# Camera-Board.net
KiCad netlist of a schematic drawn in EAGLE
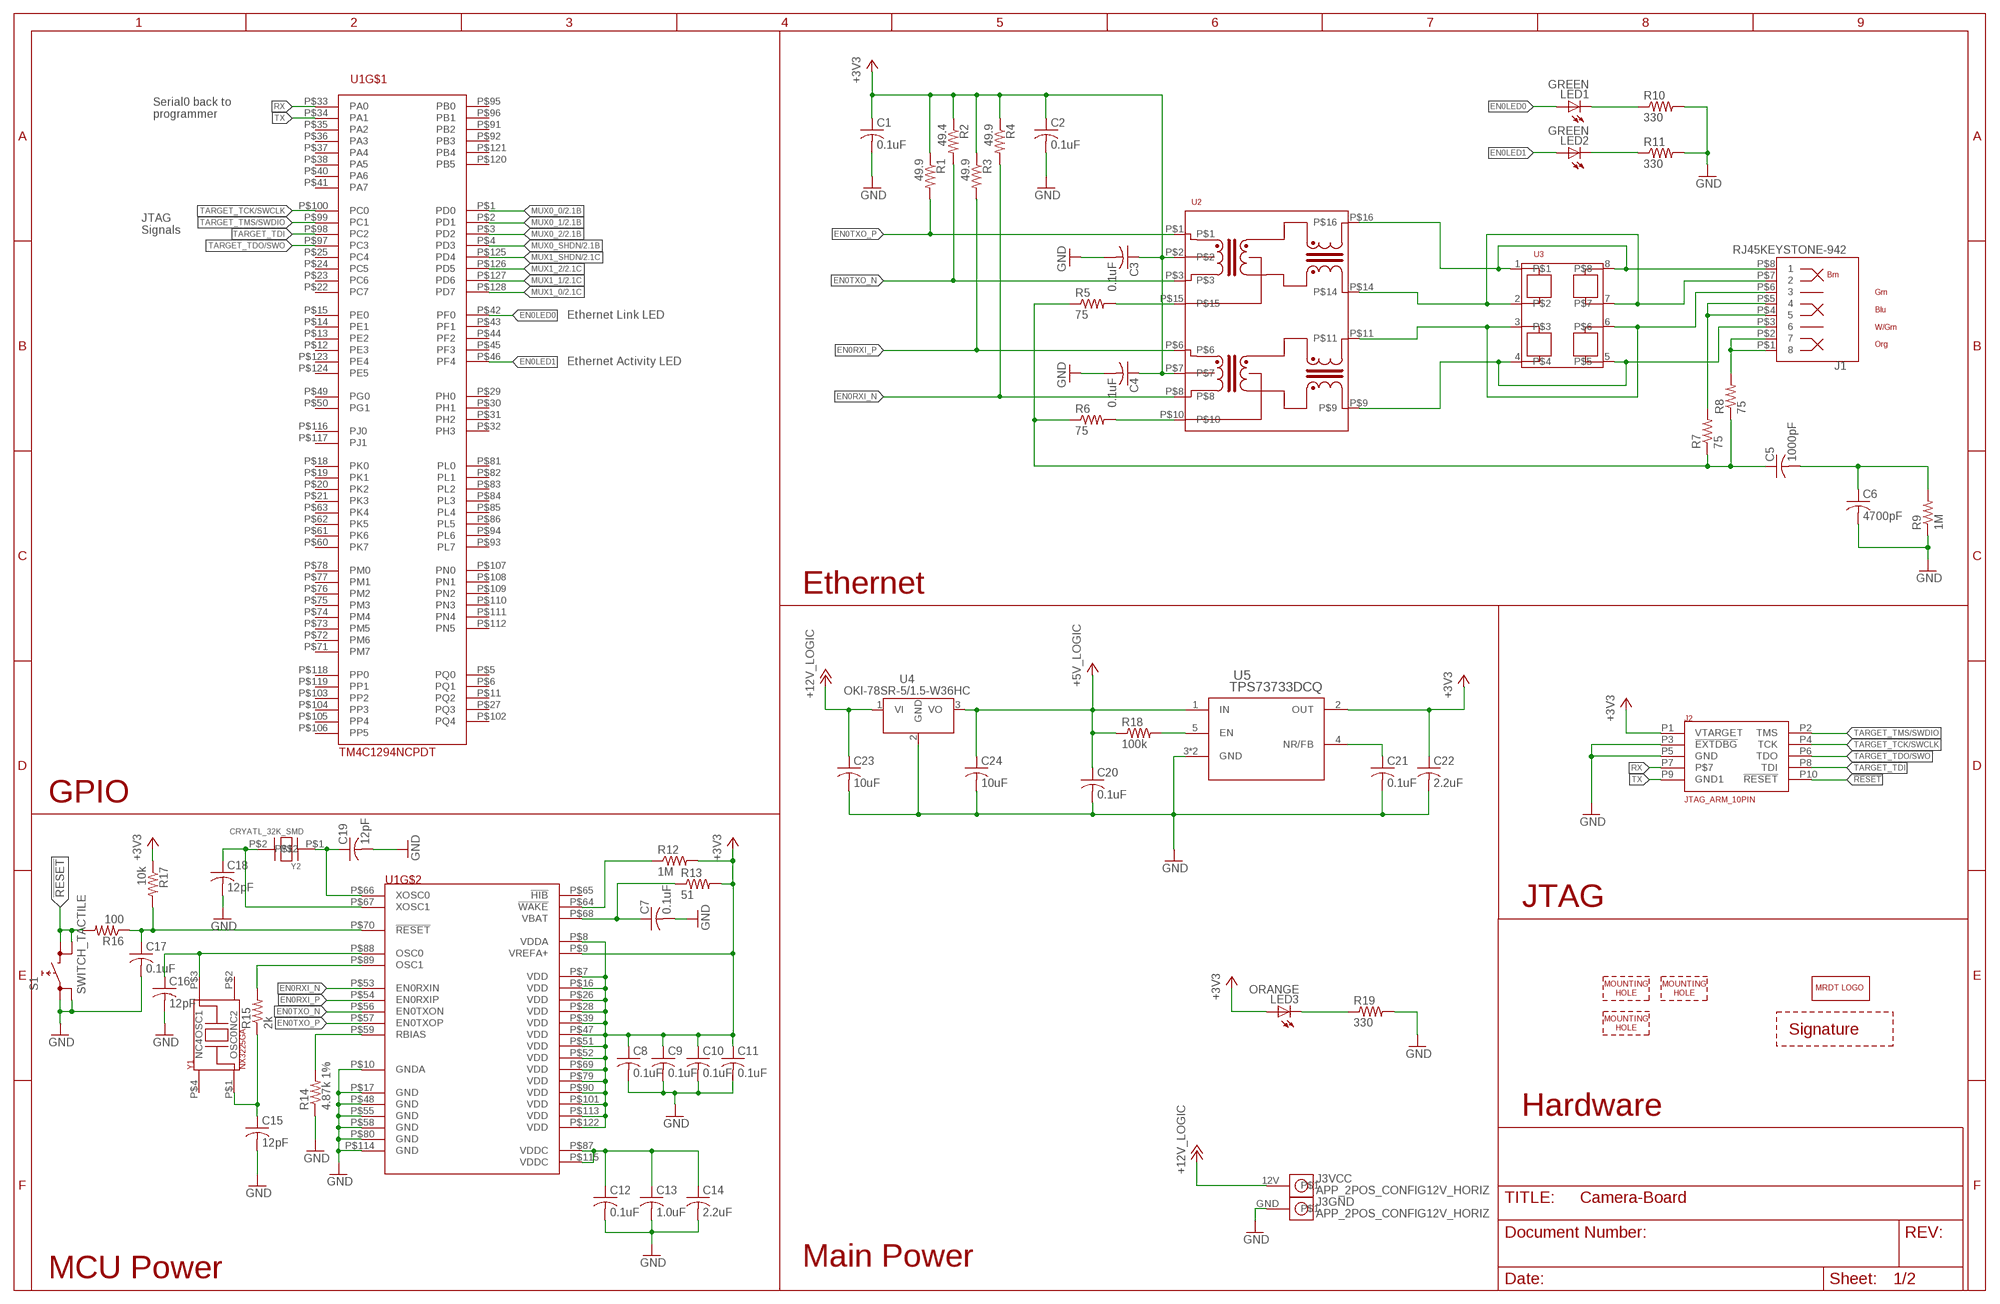
[diagram p0: schematic, sheet 1]
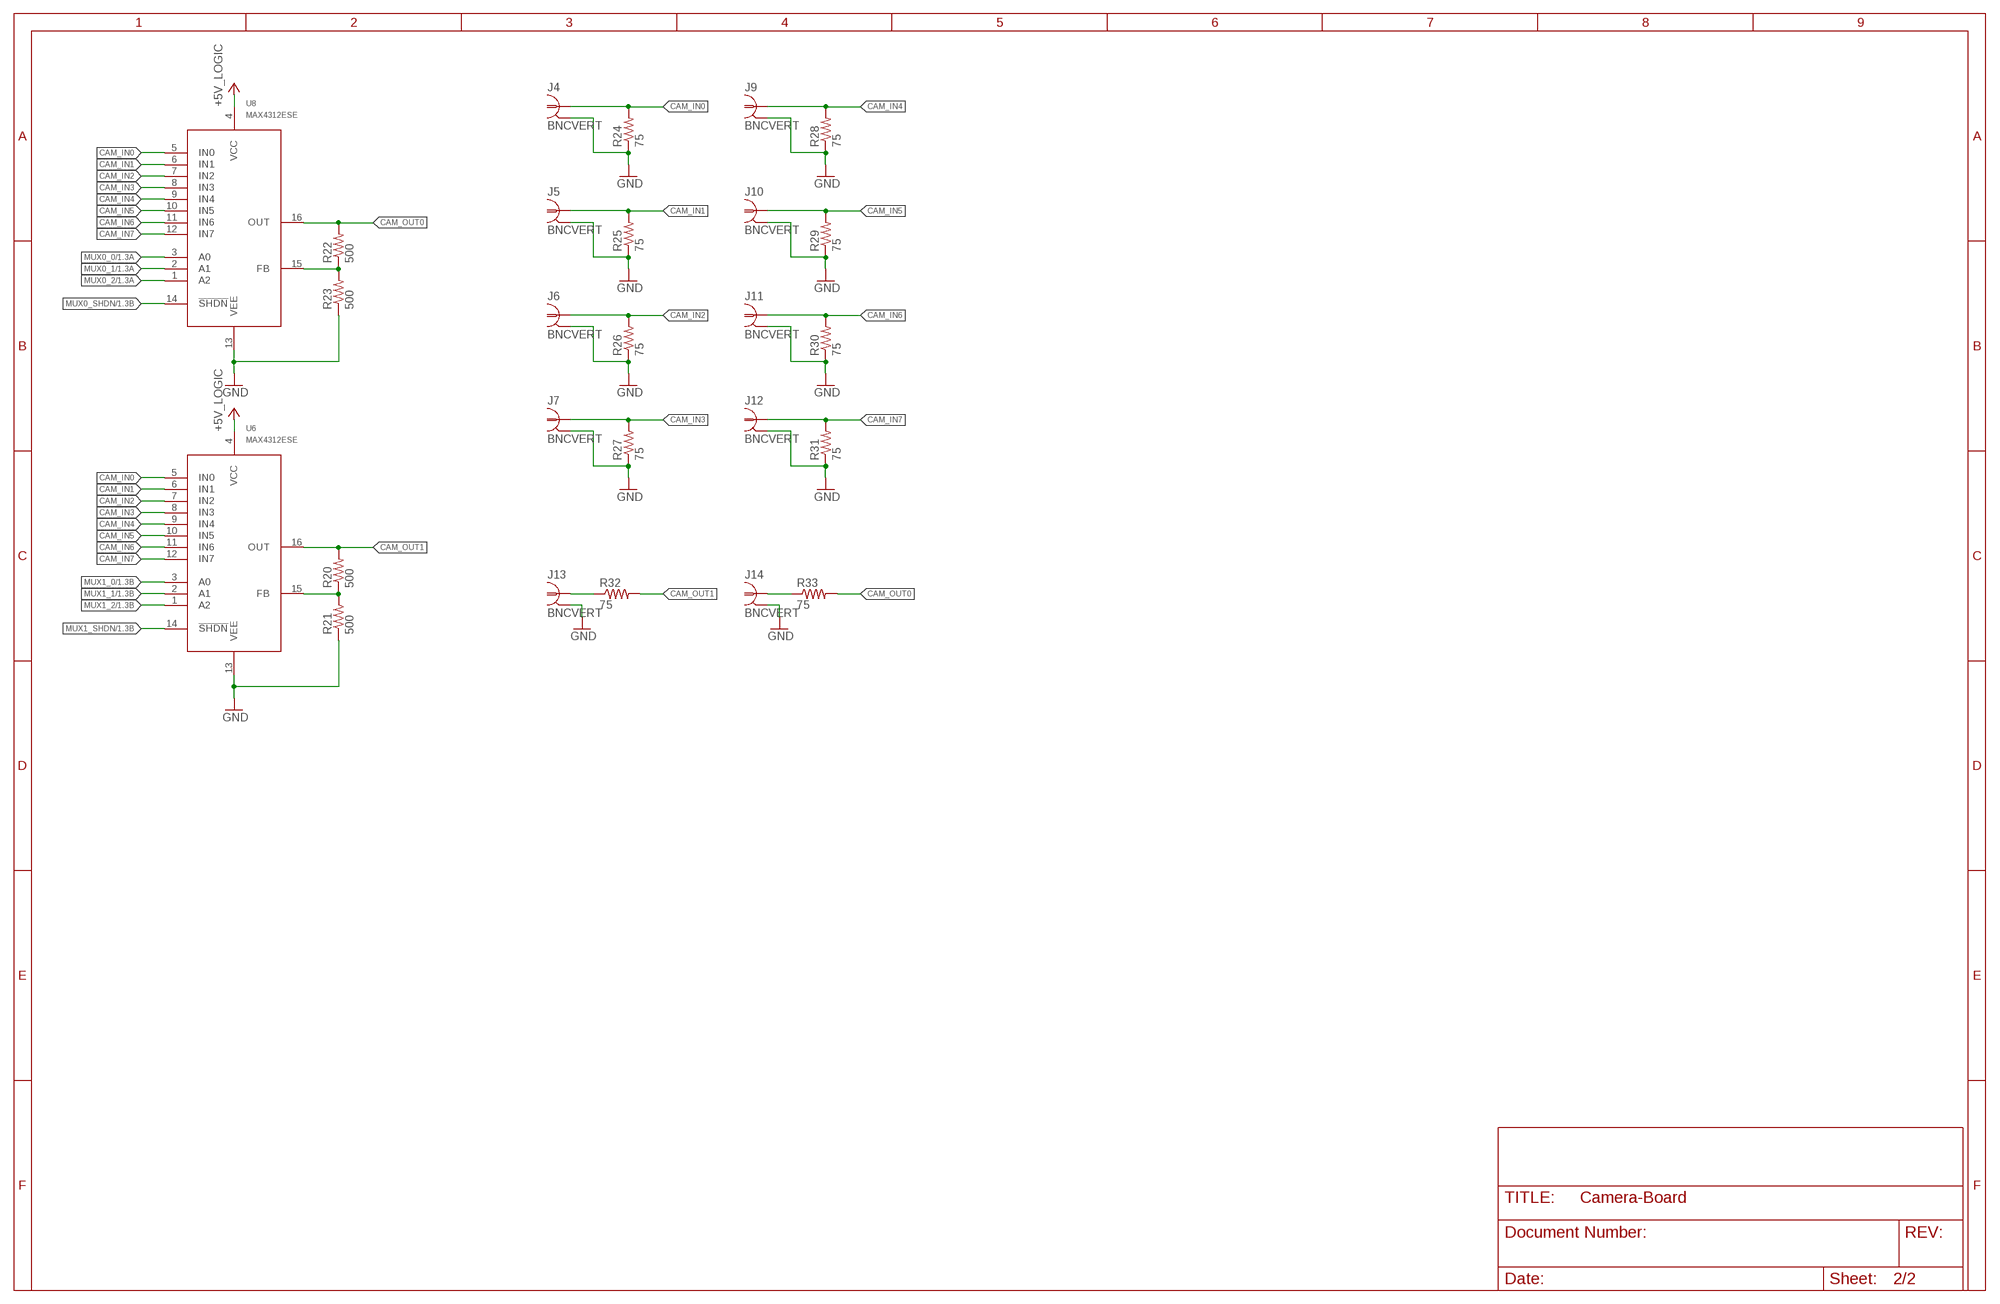
[diagram p1: schematic, sheet 2]

(export (version "E")
  (design (tool "Eeschema 10.0.6"))
  (components
    (comp (ref "J4")
      (value "BNCVERT")
      (footprint "eagle-import:MOLEX-0731711900-BNC")
      (libsource (lib "eagle-import") (part "BNCVERT"))
    )
    (comp (ref "J5")
      (value "BNCVERT")
      (footprint "eagle-import:MOLEX-0731711900-BNC")
      (libsource (lib "eagle-import") (part "BNCVERT"))
    )
    (comp (ref "J6")
      (value "BNCVERT")
      (footprint "eagle-import:MOLEX-0731711900-BNC")
      (libsource (lib "eagle-import") (part "BNCVERT"))
    )
    (comp (ref "J7")
      (value "BNCVERT")
      (footprint "eagle-import:MOLEX-0731711900-BNC")
      (libsource (lib "eagle-import") (part "BNCVERT"))
    )
    (comp (ref "J9")
      (value "BNCVERT")
      (footprint "eagle-import:MOLEX-0731711900-BNC")
      (libsource (lib "eagle-import") (part "BNCVERT"))
    )
    (comp (ref "J10")
      (value "BNCVERT")
      (footprint "eagle-import:MOLEX-0731711900-BNC")
      (libsource (lib "eagle-import") (part "BNCVERT"))
    )
    (comp (ref "J11")
      (value "BNCVERT")
      (footprint "eagle-import:MOLEX-0731711900-BNC")
      (libsource (lib "eagle-import") (part "BNCVERT"))
    )
    (comp (ref "J12")
      (value "BNCVERT")
      (footprint "eagle-import:MOLEX-0731711900-BNC")
      (libsource (lib "eagle-import") (part "BNCVERT"))
    )
    (comp (ref "J13")
      (value "BNCVERT")
      (footprint "eagle-import:MOLEX-0731711900-BNC")
      (libsource (lib "eagle-import") (part "BNCVERT"))
    )
    (comp (ref "J14")
      (value "BNCVERT")
      (footprint "eagle-import:MOLEX-0731711900-BNC")
      (libsource (lib "eagle-import") (part "BNCVERT"))
    )
    (comp (ref "R20")
      (value "500")
      (footprint "eagle-import:R0603")
      (libsource (lib "eagle-import") (part "resistor_R-US_R0603"))
    )
    (comp (ref "R21")
      (value "500")
      (footprint "eagle-import:R0603")
      (libsource (lib "eagle-import") (part "resistor_R-US_R0603"))
    )
    (comp (ref "R22")
      (value "500")
      (footprint "eagle-import:R0603")
      (libsource (lib "eagle-import") (part "resistor_R-US_R0603"))
    )
    (comp (ref "R23")
      (value "500")
      (footprint "eagle-import:R0603")
      (libsource (lib "eagle-import") (part "resistor_R-US_R0603"))
    )
    (comp (ref "R24")
      (value "75")
      (footprint "eagle-import:R0603")
      (libsource (lib "eagle-import") (part "resistor_R-US_R0603"))
    )
    (comp (ref "R25")
      (value "75")
      (footprint "eagle-import:R0603")
      (libsource (lib "eagle-import") (part "resistor_R-US_R0603"))
    )
    (comp (ref "R26")
      (value "75")
      (footprint "eagle-import:R0603")
      (libsource (lib "eagle-import") (part "resistor_R-US_R0603"))
    )
    (comp (ref "R27")
      (value "75")
      (footprint "eagle-import:R0603")
      (libsource (lib "eagle-import") (part "resistor_R-US_R0603"))
    )
    (comp (ref "R28")
      (value "75")
      (footprint "eagle-import:R0603")
      (libsource (lib "eagle-import") (part "resistor_R-US_R0603"))
    )
    (comp (ref "R29")
      (value "75")
      (footprint "eagle-import:R0603")
      (libsource (lib "eagle-import") (part "resistor_R-US_R0603"))
    )
    (comp (ref "R30")
      (value "75")
      (footprint "eagle-import:R0603")
      (libsource (lib "eagle-import") (part "resistor_R-US_R0603"))
    )
    (comp (ref "R31")
      (value "75")
      (footprint "eagle-import:R0603")
      (libsource (lib "eagle-import") (part "resistor_R-US_R0603"))
    )
    (comp (ref "R32")
      (value "75")
      (footprint "eagle-import:R0603")
      (libsource (lib "eagle-import") (part "resistor_R-US_R0603"))
    )
    (comp (ref "R33")
      (value "75")
      (footprint "eagle-import:R0603")
      (libsource (lib "eagle-import") (part "resistor_R-US_R0603"))
    )
    (comp (ref "U6")
      (value "MAX4312ESE")
      (footprint "eagle-import:SOIC16")
      (libsource (lib "eagle-import") (part "MAX4312E?ES"))
    )
    (comp (ref "U8")
      (value "MAX4312ESE")
      (footprint "eagle-import:SOIC16")
      (libsource (lib "eagle-import") (part "MAX4312E?ES"))
    )
    (comp (ref "C1")
      (value "0.1uF")
      (footprint "eagle-import:C0603")
      (libsource (lib "eagle-import") (part "C-USC0603"))
    )
    (comp (ref "C2")
      (value "0.1uF")
      (footprint "eagle-import:C0603")
      (libsource (lib "eagle-import") (part "C-USC0603"))
    )
    (comp (ref "C3")
      (value "0.1uF")
      (footprint "eagle-import:C0603")
      (libsource (lib "eagle-import") (part "C-USC0603"))
    )
    (comp (ref "C4")
      (value "0.1uF")
      (footprint "eagle-import:C0603")
      (libsource (lib "eagle-import") (part "C-USC0603"))
    )
    (comp (ref "C5")
      (value "1000pF")
      (footprint "eagle-import:C0603")
      (libsource (lib "eagle-import") (part "C-USC0603"))
    )
    (comp (ref "C6")
      (value "4700pF")
      (footprint "eagle-import:C1206")
      (libsource (lib "eagle-import") (part "C-USC1206"))
    )
    (comp (ref "C7")
      (value "0.1uF")
      (footprint "eagle-import:C0603")
      (libsource (lib "eagle-import") (part "C-USC0603"))
    )
    (comp (ref "C8")
      (value "0.1uF")
      (footprint "eagle-import:C0603")
      (libsource (lib "eagle-import") (part "C-USC0603"))
    )
    (comp (ref "C9")
      (value "0.1uF")
      (footprint "eagle-import:C0603")
      (libsource (lib "eagle-import") (part "C-USC0603"))
    )
    (comp (ref "C10")
      (value "0.1uF")
      (footprint "eagle-import:C0603")
      (libsource (lib "eagle-import") (part "C-USC0603"))
    )
    (comp (ref "C11")
      (value "0.1uF")
      (footprint "eagle-import:C0603")
      (libsource (lib "eagle-import") (part "C-USC0603"))
    )
    (comp (ref "C12")
      (value "0.1uF")
      (footprint "eagle-import:C0603")
      (libsource (lib "eagle-import") (part "C-USC0603"))
    )
    (comp (ref "C13")
      (value "1.0uF")
      (footprint "eagle-import:C0603")
      (libsource (lib "eagle-import") (part "C-USC0603"))
    )
    (comp (ref "C14")
      (value "2.2uF")
      (footprint "eagle-import:C0603")
      (libsource (lib "eagle-import") (part "C-USC0603"))
    )
    (comp (ref "C15")
      (value "12pF")
      (footprint "eagle-import:C0603")
      (libsource (lib "eagle-import") (part "C-USC0603"))
    )
    (comp (ref "C16")
      (value "12pF")
      (footprint "eagle-import:C0603")
      (libsource (lib "eagle-import") (part "C-USC0603"))
    )
    (comp (ref "C17")
      (value "0.1uF")
      (footprint "eagle-import:C0603")
      (libsource (lib "eagle-import") (part "C-USC0603"))
    )
    (comp (ref "C18")
      (value "12pF")
      (footprint "eagle-import:C0603")
      (libsource (lib "eagle-import") (part "C-USC0603"))
    )
    (comp (ref "C19")
      (value "12pF")
      (footprint "eagle-import:C0603")
      (libsource (lib "eagle-import") (part "C-USC0603"))
    )
    (comp (ref "C20")
      (value "0.1uF")
      (footprint "eagle-import:C0603")
      (libsource (lib "eagle-import") (part "C-USC0603"))
    )
    (comp (ref "C21")
      (value "0.1uF")
      (footprint "eagle-import:C0603")
      (libsource (lib "eagle-import") (part "C-USC0603"))
    )
    (comp (ref "C22")
      (value "2.2uF")
      (footprint "eagle-import:C0603")
      (libsource (lib "eagle-import") (part "C-USC0603"))
    )
    (comp (ref "C23")
      (value "10uF")
      (footprint "eagle-import:C1206")
      (libsource (lib "eagle-import") (part "C-USC1206"))
    )
    (comp (ref "C24")
      (value "10uF")
      (footprint "eagle-import:C1206")
      (libsource (lib "eagle-import") (part "C-USC1206"))
    )
    (comp (ref "J1")
      (value "RJ45KEYSTONE-942")
      (footprint "eagle-import:KEYSTONE-942")
      (libsource (lib "eagle-import") (part "RJ45KEYSTONE-942"))
    )
    (comp (ref "J2")
      (value "JTAG_ARM_10PIN")
      (footprint "eagle-import:CON_2X5_50MIL")
      (fields (field (name "PARTNO") "M50-3600542 "))
      (libsource (lib "eagle-import") (part "JTAG_ARM_10PIN"))
    )
    (comp (ref "J3")
      (value "APP_2POS_CONFIG12V_HORIZ")
      (footprint "eagle-import:APP45_12V_HORIZ_CONFIG")
      (libsource (lib "eagle-import") (part "APP_2POS_CONFIG12V_HORIZ"))
    )
    (comp (ref "LED1")
      (value "GREEN")
      (footprint "eagle-import:CHIP-LED0603")
      (libsource (lib "eagle-import") (part "LEDCHIP-LED0603"))
    )
    (comp (ref "LED2")
      (value "GREEN")
      (footprint "eagle-import:CHIP-LED0603")
      (libsource (lib "eagle-import") (part "LEDCHIP-LED0603"))
    )
    (comp (ref "LED3")
      (value "ORANGE")
      (footprint "eagle-import:CHIP-LED0603")
      (libsource (lib "eagle-import") (part "LEDCHIP-LED0603"))
    )
    (comp (ref "R1")
      (value "49.9")
      (footprint "eagle-import:R0603")
      (libsource (lib "eagle-import") (part "R-US_R0603"))
    )
    (comp (ref "R2")
      (value "49.4")
      (footprint "eagle-import:R0603")
      (libsource (lib "eagle-import") (part "resistor_R-US_R0603"))
    )
    (comp (ref "R3")
      (value "49.9")
      (footprint "eagle-import:R0603")
      (libsource (lib "eagle-import") (part "resistor_R-US_R0603"))
    )
    (comp (ref "R4")
      (value "49.9")
      (footprint "eagle-import:R0603")
      (libsource (lib "eagle-import") (part "resistor_R-US_R0603"))
    )
    (comp (ref "R5")
      (value "75")
      (footprint "eagle-import:R0603")
      (libsource (lib "eagle-import") (part "resistor_R-US_R0603"))
    )
    (comp (ref "R6")
      (value "75")
      (footprint "eagle-import:R0603")
      (libsource (lib "eagle-import") (part "resistor_R-US_R0603"))
    )
    (comp (ref "R7")
      (value "75")
      (footprint "eagle-import:R0603")
      (libsource (lib "eagle-import") (part "resistor_R-US_R0603"))
    )
    (comp (ref "R8")
      (value "75")
      (footprint "eagle-import:R0603")
      (libsource (lib "eagle-import") (part "resistor_R-US_R0603"))
    )
    (comp (ref "R9")
      (value "1M")
      (footprint "eagle-import:R1206")
      (libsource (lib "eagle-import") (part "resistor_R-US_R1206"))
    )
    (comp (ref "R10")
      (value "330")
      (footprint "eagle-import:R0603")
      (libsource (lib "eagle-import") (part "resistor_R-US_R0603"))
    )
    (comp (ref "R11")
      (value "330")
      (footprint "eagle-import:R0603")
      (libsource (lib "eagle-import") (part "resistor_R-US_R0603"))
    )
    (comp (ref "R12")
      (value "1M")
      (footprint "eagle-import:R0603")
      (libsource (lib "eagle-import") (part "resistor_R-US_R0603"))
    )
    (comp (ref "R13")
      (value "51")
      (footprint "eagle-import:R0603")
      (libsource (lib "eagle-import") (part "resistor_R-US_R0603"))
    )
    (comp (ref "R14")
      (value "4.87k 1%")
      (footprint "eagle-import:R0603")
      (libsource (lib "eagle-import") (part "resistor_R-US_R0603"))
    )
    (comp (ref "R15")
      (value "2k")
      (footprint "eagle-import:R0603")
      (libsource (lib "eagle-import") (part "resistor_R-US_R0603"))
    )
    (comp (ref "R16")
      (value "100")
      (footprint "eagle-import:R0603")
      (libsource (lib "eagle-import") (part "resistor_R-US_R0603"))
    )
    (comp (ref "R17")
      (value "10k")
      (footprint "eagle-import:R0603")
      (libsource (lib "eagle-import") (part "resistor_R-US_R0603"))
    )
    (comp (ref "R18")
      (value "100k")
      (footprint "eagle-import:R0603")
      (libsource (lib "eagle-import") (part "resistor_R-US_R0603"))
    )
    (comp (ref "R19")
      (value "330")
      (footprint "eagle-import:R0603")
      (libsource (lib "eagle-import") (part "resistor_R-US_R0603"))
    )
    (comp (ref "S1")
      (value "SWITCH_TACTILE")
      (footprint "eagle-import:SWITCH_6MM_6MM_TE_CON_SMD")
      (libsource (lib "eagle-import") (part "SWITCH_TACTILE"))
    )
    (comp (ref "U$1")
      (value "MRDT_LOGO")
      (footprint "eagle-import:MRDT_LOGO")
      (libsource (lib "eagle-import") (part "MRDT_LOGO"))
    )
    (comp (ref "U$2")
      (value "MOUNTING_HOLE#6")
      (footprint "eagle-import:#6_SCREW")
      (libsource (lib "eagle-import") (part "MOUNTING_HOLE#6"))
    )
    (comp (ref "U$3")
      (value "MOUNTING_HOLE#6")
      (footprint "eagle-import:#6_SCREW")
      (libsource (lib "eagle-import") (part "MOUNTING_HOLE#6"))
    )
    (comp (ref "U$4")
      (value "MOUNTING_HOLE#6")
      (footprint "eagle-import:#6_SCREW")
      (libsource (lib "eagle-import") (part "MOUNTING_HOLE#6"))
    )
    (comp (ref "U$8")
      (value "SIG3")
      (footprint "eagle-import:SIG3")
      (libsource (lib "eagle-import") (part "SIG3"))
    )
    (comp (ref "U1")
      (value "TM4C1294NCPDT")
      (footprint "eagle-import:TQFP-128")
      (libsource (lib "eagle-import") (part "TM4C1294NCPDT"))
    )
    (comp (ref "U2")
      (value "HX1198FNL")
      (footprint "eagle-import:HX1198FNL")
      (libsource (lib "eagle-import") (part "HX1198FNL"))
    )
    (comp (ref "U3")
      (value "SLVU2.8-4")
      (footprint "eagle-import:SOIC8")
      (libsource (lib "eagle-import") (part "SLVU2.8-4"))
    )
    (comp (ref "U4")
      (value "OKI-78SR-5/1.5-W36HC")
      (footprint "eagle-import:OKI-78SR_HORIZ")
      (libsource (lib "eagle-import") (part "OKI-78SR-/1.5-W36?CH5"))
    )
    (comp (ref "U5")
      (value "TPS73733DCQ")
      (footprint "eagle-import:SOT-223-6")
      (libsource (lib "eagle-import") (part "TPS73733DCQ"))
    )
    (comp (ref "Y1")
      (value "NX3225GA")
      (footprint "eagle-import:NDK3.2X2.5")
      (libsource (lib "eagle-import") (part "NX3225GA"))
    )
    (comp (ref "Y2")
      (value "CRYATL_32K_SMD")
      (footprint "eagle-import:CRYSTAL_32K_SMD")
      (libsource (lib "eagle-import") (part "CRYATL_32K_SMD"))
    )
  )
  (nets
    (net (code "1") (name "+3V3") (class "Default")
      (node (ref "C1") (pin "1") (pinfunction "1_1") (pintype "passive"))
      (node (ref "C10") (pin "1") (pinfunction "1_1") (pintype "passive"))
      (node (ref "C11") (pin "1") (pinfunction "1_1") (pintype "passive"))
      (node (ref "C2") (pin "1") (pinfunction "1_1") (pintype "passive"))
      (node (ref "C22") (pin "1") (pinfunction "1_1") (pintype "passive"))
      (node (ref "C3") (pin "1") (pinfunction "1_1") (pintype "passive"))
      (node (ref "C4") (pin "1") (pinfunction "1_1") (pintype "passive"))
      (node (ref "C8") (pin "1") (pinfunction "1_1") (pintype "passive"))
      (node (ref "C9") (pin "1") (pinfunction "1_1") (pintype "passive"))
      (node (ref "J2") (pin "P1") (pinfunction "VTARGET_P1") (pintype "bidirectional"))
      (node (ref "LED3") (pin "A") (pinfunction "A_A") (pintype "passive"))
      (node (ref "R1") (pin "1") (pinfunction "1_1") (pintype "passive"))
      (node (ref "R12") (pin "2") (pinfunction "2_2") (pintype "passive"))
      (node (ref "R13") (pin "2") (pinfunction "2_2") (pintype "passive"))
      (node (ref "R17") (pin "1") (pinfunction "1_1") (pintype "passive"))
      (node (ref "R2") (pin "1") (pinfunction "1_1") (pintype "passive"))
      (node (ref "R3") (pin "1") (pinfunction "1_1") (pintype "passive"))
      (node (ref "R4") (pin "1") (pinfunction "1_1") (pintype "passive"))
      (node (ref "U1") (pin "P$101") (pinfunction "VDD_P$101") (pintype "bidirectional"))
      (node (ref "U1") (pin "P$113") (pinfunction "VDD_P$113") (pintype "bidirectional"))
      (node (ref "U1") (pin "P$122") (pinfunction "VDD_P$122") (pintype "bidirectional"))
      (node (ref "U1") (pin "P$16") (pinfunction "VDD_P$16") (pintype "bidirectional"))
      (node (ref "U1") (pin "P$26") (pinfunction "VDD_P$26") (pintype "bidirectional"))
      (node (ref "U1") (pin "P$28") (pinfunction "VDD_P$28") (pintype "bidirectional"))
      (node (ref "U1") (pin "P$39") (pinfunction "VDD_P$39") (pintype "bidirectional"))
      (node (ref "U1") (pin "P$47") (pinfunction "VDD_P$47") (pintype "bidirectional"))
      (node (ref "U1") (pin "P$51") (pinfunction "VDD_P$51") (pintype "bidirectional"))
      (node (ref "U1") (pin "P$52") (pinfunction "VDD_P$52") (pintype "bidirectional"))
      (node (ref "U1") (pin "P$69") (pinfunction "VDD_P$69") (pintype "bidirectional"))
      (node (ref "U1") (pin "P$7") (pinfunction "VDD_P$7") (pintype "bidirectional"))
      (node (ref "U1") (pin "P$79") (pinfunction "VDD_P$79") (pintype "bidirectional"))
      (node (ref "U1") (pin "P$8") (pinfunction "VDDA_P$8") (pintype "bidirectional"))
      (node (ref "U1") (pin "P$9") (pinfunction "VREFA+_P$9") (pintype "bidirectional"))
      (node (ref "U1") (pin "P$90") (pinfunction "VDD_P$90") (pintype "bidirectional"))
      (node (ref "U2") (pin "P$2") (pinfunction "P$2_P$2") (pintype "bidirectional"))
      (node (ref "U2") (pin "P$7") (pinfunction "P$7_P$7") (pintype "bidirectional"))
      (node (ref "U5") (pin "2") (pinfunction "OUT_2") (pintype "output"))
    )
    (net (code "2") (name "+5V_LOGIC") (class "Default")
      (node (ref "C20") (pin "1") (pinfunction "1_1") (pintype "passive"))
      (node (ref "C24") (pin "1") (pinfunction "1_1") (pintype "passive"))
      (node (ref "R18") (pin "1") (pinfunction "1_1") (pintype "passive"))
      (node (ref "U4") (pin "3") (pinfunction "VO_3") (pintype "bidirectional"))
      (node (ref "U5") (pin "1") (pinfunction "IN_1") (pintype "input"))
      (node (ref "U6") (pin "4") (pinfunction "VCC_4") (pintype "power_in"))
      (node (ref "U8") (pin "4") (pinfunction "VCC_4") (pintype "power_in"))
    )
    (net (code "3") (name "+12V_LOGIC") (class "Default")
      (node (ref "C23") (pin "1") (pinfunction "1_1") (pintype "passive"))
      (node (ref "J3") (pin "12V") (pinfunction "P$1_12V") (pintype "bidirectional"))
      (node (ref "U4") (pin "1") (pinfunction "VI_1") (pintype "bidirectional"))
    )
    (net (code "4") (name "CAM_IN0") (class "Default")
      (node (ref "J4") (pin "P$1") (pinfunction "1_P$1") (pintype "passive"))
      (node (ref "R24") (pin "2") (pinfunction "2_2") (pintype "passive"))
      (node (ref "U6") (pin "5") (pinfunction "IN0_5") (pintype "input"))
      (node (ref "U8") (pin "5") (pinfunction "IN0_5") (pintype "input"))
    )
    (net (code "5") (name "CAM_IN1") (class "Default")
      (node (ref "J5") (pin "P$1") (pinfunction "1_P$1") (pintype "passive"))
      (node (ref "R25") (pin "2") (pinfunction "2_2") (pintype "passive"))
      (node (ref "U6") (pin "6") (pinfunction "IN1_6") (pintype "input"))
      (node (ref "U8") (pin "6") (pinfunction "IN1_6") (pintype "input"))
    )
    (net (code "6") (name "CAM_IN2") (class "Default")
      (node (ref "J6") (pin "P$1") (pinfunction "1_P$1") (pintype "passive"))
      (node (ref "R26") (pin "2") (pinfunction "2_2") (pintype "passive"))
      (node (ref "U6") (pin "7") (pinfunction "IN2_7") (pintype "input"))
      (node (ref "U8") (pin "7") (pinfunction "IN2_7") (pintype "input"))
    )
    (net (code "7") (name "CAM_IN3") (class "Default")
      (node (ref "J7") (pin "P$1") (pinfunction "1_P$1") (pintype "passive"))
      (node (ref "R27") (pin "2") (pinfunction "2_2") (pintype "passive"))
      (node (ref "U6") (pin "8") (pinfunction "IN3_8") (pintype "input"))
      (node (ref "U8") (pin "8") (pinfunction "IN3_8") (pintype "input"))
    )
    (net (code "8") (name "CAM_IN4") (class "Default")
      (node (ref "J9") (pin "P$1") (pinfunction "1_P$1") (pintype "passive"))
      (node (ref "R28") (pin "2") (pinfunction "2_2") (pintype "passive"))
      (node (ref "U6") (pin "9") (pinfunction "IN4_9") (pintype "input"))
      (node (ref "U8") (pin "9") (pinfunction "IN4_9") (pintype "input"))
    )
    (net (code "9") (name "CAM_IN5") (class "Default")
      (node (ref "J10") (pin "P$1") (pinfunction "1_P$1") (pintype "passive"))
      (node (ref "R29") (pin "2") (pinfunction "2_2") (pintype "passive"))
      (node (ref "U6") (pin "10") (pinfunction "IN5_10") (pintype "input"))
      (node (ref "U8") (pin "10") (pinfunction "IN5_10") (pintype "input"))
    )
    (net (code "10") (name "CAM_IN6") (class "Default")
      (node (ref "J11") (pin "P$1") (pinfunction "1_P$1") (pintype "passive"))
      (node (ref "R30") (pin "2") (pinfunction "2_2") (pintype "passive"))
      (node (ref "U6") (pin "11") (pinfunction "IN6_11") (pintype "input"))
      (node (ref "U8") (pin "11") (pinfunction "IN6_11") (pintype "input"))
    )
    (net (code "11") (name "CAM_IN7") (class "Default")
      (node (ref "J12") (pin "P$1") (pinfunction "1_P$1") (pintype "passive"))
      (node (ref "R31") (pin "2") (pinfunction "2_2") (pintype "passive"))
      (node (ref "U6") (pin "12") (pinfunction "IN7_12") (pintype "input"))
      (node (ref "U8") (pin "12") (pinfunction "IN7_12") (pintype "input"))
    )
    (net (code "12") (name "CAM_OUT0") (class "Default")
      (node (ref "R22") (pin "2") (pinfunction "2_2") (pintype "passive"))
      (node (ref "R33") (pin "2") (pinfunction "2_2") (pintype "passive"))
      (node (ref "U8") (pin "16") (pinfunction "OUT_16") (pintype "output"))
    )
    (net (code "13") (name "CAM_OUT1") (class "Default")
      (node (ref "R20") (pin "2") (pinfunction "2_2") (pintype "passive"))
      (node (ref "R32") (pin "2") (pinfunction "2_2") (pintype "passive"))
      (node (ref "U6") (pin "16") (pinfunction "OUT_16") (pintype "output"))
    )
    (net (code "14") (name "EN0LED0") (class "Default")
      (node (ref "LED1") (pin "A") (pinfunction "A_A") (pintype "passive"))
      (node (ref "U1") (pin "P$42") (pinfunction "PF0_P$42") (pintype "bidirectional"))
    )
    (net (code "15") (name "EN0LED1") (class "Default")
      (node (ref "LED2") (pin "A") (pinfunction "A_A") (pintype "passive"))
      (node (ref "U1") (pin "P$46") (pinfunction "PF4_P$46") (pintype "bidirectional"))
    )
    (net (code "16") (name "EN0RXI_N") (class "Default")
      (node (ref "R4") (pin "2") (pinfunction "2_2") (pintype "passive"))
      (node (ref "U1") (pin "P$53") (pinfunction "EN0RXIN_P$53") (pintype "bidirectional"))
      (node (ref "U2") (pin "P$8") (pinfunction "P$8_P$8") (pintype "bidirectional"))
    )
    (net (code "17") (name "EN0RXI_P") (class "Default")
      (node (ref "R3") (pin "2") (pinfunction "2_2") (pintype "passive"))
      (node (ref "U1") (pin "P$54") (pinfunction "EN0RXIP_P$54") (pintype "bidirectional"))
      (node (ref "U2") (pin "P$6") (pinfunction "P$6_P$6") (pintype "bidirectional"))
    )
    (net (code "18") (name "EN0TXO_N") (class "Default")
      (node (ref "R2") (pin "2") (pinfunction "2_2") (pintype "passive"))
      (node (ref "U1") (pin "P$56") (pinfunction "EN0TXON_P$56") (pintype "bidirectional"))
      (node (ref "U2") (pin "P$3") (pinfunction "P$3_P$3") (pintype "bidirectional"))
    )
    (net (code "19") (name "EN0TXO_P") (class "Default")
      (node (ref "R1") (pin "2") (pinfunction "2_2") (pintype "passive"))
      (node (ref "U1") (pin "P$57") (pinfunction "EN0TXOP_P$57") (pintype "bidirectional"))
      (node (ref "U2") (pin "P$1") (pinfunction "P$1_P$1") (pintype "bidirectional"))
    )
    (net (code "20") (name "GND") (class "Default")
      (node (ref "C1") (pin "2") (pinfunction "2_2") (pintype "passive"))
      (node (ref "C10") (pin "2") (pinfunction "2_2") (pintype "passive"))
      (node (ref "C11") (pin "2") (pinfunction "2_2") (pintype "passive"))
      (node (ref "C12") (pin "2") (pinfunction "2_2") (pintype "passive"))
      (node (ref "C13") (pin "2") (pinfunction "2_2") (pintype "passive"))
      (node (ref "C14") (pin "2") (pinfunction "2_2") (pintype "passive"))
      (node (ref "C15") (pin "2") (pinfunction "2_2") (pintype "passive"))
      (node (ref "C16") (pin "2") (pinfunction "2_2") (pintype "passive"))
      (node (ref "C17") (pin "2") (pinfunction "2_2") (pintype "passive"))
      (node (ref "C18") (pin "2") (pinfunction "2_2") (pintype "passive"))
      (node (ref "C19") (pin "2") (pinfunction "2_2") (pintype "passive"))
      (node (ref "C2") (pin "2") (pinfunction "2_2") (pintype "passive"))
      (node (ref "C20") (pin "2") (pinfunction "2_2") (pintype "passive"))
      (node (ref "C21") (pin "2") (pinfunction "2_2") (pintype "passive"))
      (node (ref "C22") (pin "2") (pinfunction "2_2") (pintype "passive"))
      (node (ref "C23") (pin "2") (pinfunction "2_2") (pintype "passive"))
      (node (ref "C24") (pin "2") (pinfunction "2_2") (pintype "passive"))
      (node (ref "C3") (pin "2") (pinfunction "2_2") (pintype "passive"))
      (node (ref "C4") (pin "2") (pinfunction "2_2") (pintype "passive"))
      (node (ref "C6") (pin "2") (pinfunction "2_2") (pintype "passive"))
      (node (ref "C7") (pin "2") (pinfunction "2_2") (pintype "passive"))
      (node (ref "C8") (pin "2") (pinfunction "2_2") (pintype "passive"))
      (node (ref "C9") (pin "2") (pinfunction "2_2") (pintype "passive"))
      (node (ref "J10") (pin "P$2") (pinfunction "2_P$2") (pintype "passive"))
      (node (ref "J10") (pin "P$3") (pinfunction "2_P$3") (pintype "passive"))
      (node (ref "J10") (pin "P$4") (pinfunction "2_P$4") (pintype "passive"))
      (node (ref "J10") (pin "P$5") (pinfunction "2_P$5") (pintype "passive"))
      (node (ref "J11") (pin "P$2") (pinfunction "2_P$2") (pintype "passive"))
      (node (ref "J11") (pin "P$3") (pinfunction "2_P$3") (pintype "passive"))
      (node (ref "J11") (pin "P$4") (pinfunction "2_P$4") (pintype "passive"))
      (node (ref "J11") (pin "P$5") (pinfunction "2_P$5") (pintype "passive"))
      (node (ref "J12") (pin "P$2") (pinfunction "2_P$2") (pintype "passive"))
      (node (ref "J12") (pin "P$3") (pinfunction "2_P$3") (pintype "passive"))
      (node (ref "J12") (pin "P$4") (pinfunction "2_P$4") (pintype "passive"))
      (node (ref "J12") (pin "P$5") (pinfunction "2_P$5") (pintype "passive"))
      (node (ref "J13") (pin "P$2") (pinfunction "2_P$2") (pintype "passive"))
      (node (ref "J13") (pin "P$3") (pinfunction "2_P$3") (pintype "passive"))
      (node (ref "J13") (pin "P$4") (pinfunction "2_P$4") (pintype "passive"))
      (node (ref "J13") (pin "P$5") (pinfunction "2_P$5") (pintype "passive"))
      (node (ref "J14") (pin "P$2") (pinfunction "2_P$2") (pintype "passive"))
      (node (ref "J14") (pin "P$3") (pinfunction "2_P$3") (pintype "passive"))
      (node (ref "J14") (pin "P$4") (pinfunction "2_P$4") (pintype "passive"))
      (node (ref "J14") (pin "P$5") (pinfunction "2_P$5") (pintype "passive"))
      (node (ref "J2") (pin "P3") (pinfunction "~{EXTDBG}_P3") (pintype "bidirectional"))
      (node (ref "J2") (pin "P5") (pinfunction "GND_P5") (pintype "bidirectional"))
      (node (ref "J3") (pin "GND") (pinfunction "P$1_GND") (pintype "bidirectional"))
      (node (ref "J4") (pin "P$2") (pinfunction "2_P$2") (pintype "passive"))
      (node (ref "J4") (pin "P$3") (pinfunction "2_P$3") (pintype "passive"))
      (node (ref "J4") (pin "P$4") (pinfunction "2_P$4") (pintype "passive"))
      (node (ref "J4") (pin "P$5") (pinfunction "2_P$5") (pintype "passive"))
      (node (ref "J5") (pin "P$2") (pinfunction "2_P$2") (pintype "passive"))
      (node (ref "J5") (pin "P$3") (pinfunction "2_P$3") (pintype "passive"))
      (node (ref "J5") (pin "P$4") (pinfunction "2_P$4") (pintype "passive"))
      (node (ref "J5") (pin "P$5") (pinfunction "2_P$5") (pintype "passive"))
      (node (ref "J6") (pin "P$2") (pinfunction "2_P$2") (pintype "passive"))
      (node (ref "J6") (pin "P$3") (pinfunction "2_P$3") (pintype "passive"))
      (node (ref "J6") (pin "P$4") (pinfunction "2_P$4") (pintype "passive"))
      (node (ref "J6") (pin "P$5") (pinfunction "2_P$5") (pintype "passive"))
      (node (ref "J7") (pin "P$2") (pinfunction "2_P$2") (pintype "passive"))
      (node (ref "J7") (pin "P$3") (pinfunction "2_P$3") (pintype "passive"))
      (node (ref "J7") (pin "P$4") (pinfunction "2_P$4") (pintype "passive"))
      (node (ref "J7") (pin "P$5") (pinfunction "2_P$5") (pintype "passive"))
      (node (ref "J9") (pin "P$2") (pinfunction "2_P$2") (pintype "passive"))
      (node (ref "J9") (pin "P$3") (pinfunction "2_P$3") (pintype "passive"))
      (node (ref "J9") (pin "P$4") (pinfunction "2_P$4") (pintype "passive"))
      (node (ref "J9") (pin "P$5") (pinfunction "2_P$5") (pintype "passive"))
      (node (ref "R10") (pin "2") (pinfunction "2_2") (pintype "passive"))
      (node (ref "R11") (pin "2") (pinfunction "2_2") (pintype "passive"))
      (node (ref "R14") (pin "1") (pinfunction "1_1") (pintype "passive"))
      (node (ref "R19") (pin "2") (pinfunction "2_2") (pintype "passive"))
      (node (ref "R21") (pin "1") (pinfunction "1_1") (pintype "passive"))
      (node (ref "R23") (pin "1") (pinfunction "1_1") (pintype "passive"))
      (node (ref "R24") (pin "1") (pinfunction "1_1") (pintype "passive"))
      (node (ref "R25") (pin "1") (pinfunction "1_1") (pintype "passive"))
      (node (ref "R26") (pin "1") (pinfunction "1_1") (pintype "passive"))
      (node (ref "R27") (pin "1") (pinfunction "1_1") (pintype "passive"))
      (node (ref "R28") (pin "1") (pinfunction "1_1") (pintype "passive"))
      (node (ref "R29") (pin "1") (pinfunction "1_1") (pintype "passive"))
      (node (ref "R30") (pin "1") (pinfunction "1_1") (pintype "passive"))
      (node (ref "R31") (pin "1") (pinfunction "1_1") (pintype "passive"))
      (node (ref "R9") (pin "1") (pinfunction "1_1") (pintype "passive"))
      (node (ref "S1") (pin "P$1") (pinfunction "0_P$1") (pintype "passive"))
      (node (ref "S1") (pin "P$2") (pinfunction "0_P$2") (pintype "passive"))
      (node (ref "U1") (pin "P$10") (pinfunction "GNDA_P$10") (pintype "bidirectional"))
      (node (ref "U1") (pin "P$114") (pinfunction "GND_P$114") (pintype "bidirectional"))
      (node (ref "U1") (pin "P$17") (pinfunction "GND_P$17") (pintype "bidirectional"))
      (node (ref "U1") (pin "P$48") (pinfunction "GND_P$48") (pintype "bidirectional"))
      (node (ref "U1") (pin "P$55") (pinfunction "GND_P$55") (pintype "bidirectional"))
      (node (ref "U1") (pin "P$58") (pinfunction "GND_P$58") (pintype "bidirectional"))
      (node (ref "U1") (pin "P$80") (pinfunction "GND_P$80") (pintype "bidirectional"))
      (node (ref "U4") (pin "2") (pinfunction "GND_2") (pintype "bidirectional"))
      (node (ref "U5") (pin "3") (pinfunction "GND_3") (pintype "power_in"))
      (node (ref "U5") (pin "6") (pinfunction "GND_6") (pintype "power_in"))
      (node (ref "U6") (pin "13") (pinfunction "VEE_13") (pintype "power_in"))
      (node (ref "U8") (pin "13") (pinfunction "VEE_13") (pintype "power_in"))
    )
    (net (code "21") (name "MUX0_0") (class "Default")
      (node (ref "U1") (pin "P$1") (pinfunction "PD0_P$1") (pintype "bidirectional"))
      (node (ref "U8") (pin "3") (pinfunction "A0_3") (pintype "input"))
    )
    (net (code "22") (name "MUX0_1") (class "Default")
      (node (ref "U1") (pin "P$2") (pinfunction "PD1_P$2") (pintype "bidirectional"))
      (node (ref "U8") (pin "2") (pinfunction "A1_2") (pintype "input"))
    )
    (net (code "23") (name "MUX0_2") (class "Default")
      (node (ref "U1") (pin "P$3") (pinfunction "PD2_P$3") (pintype "bidirectional"))
      (node (ref "U8") (pin "1") (pinfunction "A2_1") (pintype "input"))
    )
    (net (code "24") (name "MUX0_SHDN") (class "Default")
      (node (ref "U1") (pin "P$4") (pinfunction "PD3_P$4") (pintype "bidirectional"))
      (node (ref "U8") (pin "14") (pinfunction "~{SHDN}_14") (pintype "input"))
    )
    (net (code "25") (name "MUX1_0") (class "Default")
      (node (ref "U1") (pin "P$128") (pinfunction "PD7_P$128") (pintype "bidirectional"))
      (node (ref "U6") (pin "3") (pinfunction "A0_3") (pintype "input"))
    )
    (net (code "26") (name "MUX1_1") (class "Default")
      (node (ref "U1") (pin "P$127") (pinfunction "PD6_P$127") (pintype "bidirectional"))
      (node (ref "U6") (pin "2") (pinfunction "A1_2") (pintype "input"))
    )
    (net (code "27") (name "MUX1_2") (class "Default")
      (node (ref "U1") (pin "P$126") (pinfunction "PD5_P$126") (pintype "bidirectional"))
      (node (ref "U6") (pin "1") (pinfunction "A2_1") (pintype "input"))
    )
    (net (code "28") (name "MUX1_SHDN") (class "Default")
      (node (ref "U1") (pin "P$125") (pinfunction "PD4_P$125") (pintype "bidirectional"))
      (node (ref "U6") (pin "14") (pinfunction "~{SHDN}_14") (pintype "input"))
    )
    (net (code "29") (name "Net-(C5-Pad1)") (class "Default")
      (node (ref "C5") (pin "1") (pinfunction "1_1") (pintype "passive"))
      (node (ref "R5") (pin "1") (pinfunction "1_1") (pintype "passive"))
      (node (ref "R6") (pin "1") (pinfunction "1_1") (pintype "passive"))
      (node (ref "R7") (pin "1") (pinfunction "1_1") (pintype "passive"))
      (node (ref "R8") (pin "1") (pinfunction "1_1") (pintype "passive"))
    )
    (net (code "30") (name "Net-(C5-Pad2)") (class "Default")
      (node (ref "C5") (pin "2") (pinfunction "2_2") (pintype "passive"))
      (node (ref "C6") (pin "1") (pinfunction "1_1") (pintype "passive"))
      (node (ref "R9") (pin "2") (pinfunction "2_2") (pintype "passive"))
    )
    (net (code "31") (name "Net-(C12-Pad1)") (class "Default")
      (node (ref "C12") (pin "1") (pinfunction "1_1") (pintype "passive"))
      (node (ref "C13") (pin "1") (pinfunction "1_1") (pintype "passive"))
      (node (ref "C14") (pin "1") (pinfunction "1_1") (pintype "passive"))
      (node (ref "U1") (pin "P$115") (pinfunction "VDDC_P$115") (pintype "bidirectional"))
      (node (ref "U1") (pin "P$87") (pinfunction "VDDC_P$87") (pintype "bidirectional"))
    )
    (net (code "32") (name "Net-(J1-1)") (class "Default")
      (node (ref "J1") (pin "P$8") (pinfunction "1_P$8") (pintype "bidirectional"))
      (node (ref "U2") (pin "P$16") (pinfunction "P$16_P$16") (pintype "bidirectional"))
      (node (ref "U3") (pin "1") (pinfunction "P$1_1") (pintype "bidirectional"))
      (node (ref "U3") (pin "8") (pinfunction "P$8_8") (pintype "bidirectional"))
    )
    (net (code "33") (name "Net-(J1-2)") (class "Default")
      (node (ref "J1") (pin "P$7") (pinfunction "2_P$7") (pintype "bidirectional"))
      (node (ref "U2") (pin "P$14") (pinfunction "P$14_P$14") (pintype "bidirectional"))
      (node (ref "U3") (pin "2") (pinfunction "P$2_2") (pintype "bidirectional"))
      (node (ref "U3") (pin "7") (pinfunction "P$7_7") (pintype "bidirectional"))
    )
    (net (code "34") (name "Net-(J1-3)") (class "Default")
      (node (ref "J1") (pin "P$6") (pinfunction "3_P$6") (pintype "bidirectional"))
      (node (ref "U2") (pin "P$11") (pinfunction "P$11_P$11") (pintype "bidirectional"))
      (node (ref "U3") (pin "3") (pinfunction "P$3_3") (pintype "bidirectional"))
      (node (ref "U3") (pin "6") (pinfunction "P$6_6") (pintype "bidirectional"))
    )
    (net (code "35") (name "Net-(J1-4)") (class "Default")
      (node (ref "J1") (pin "P$4") (pinfunction "5_P$4") (pintype "bidirectional"))
      (node (ref "J1") (pin "P$5") (pinfunction "4_P$5") (pintype "bidirectional"))
      (node (ref "R7") (pin "2") (pinfunction "2_2") (pintype "passive"))
    )
    (net (code "36") (name "Net-(J1-6)") (class "Default")
      (node (ref "J1") (pin "P$3") (pinfunction "6_P$3") (pintype "bidirectional"))
      (node (ref "U2") (pin "P$9") (pinfunction "P$9_P$9") (pintype "bidirectional"))
      (node (ref "U3") (pin "4") (pinfunction "P$4_4") (pintype "bidirectional"))
      (node (ref "U3") (pin "5") (pinfunction "P$5_5") (pintype "bidirectional"))
    )
    (net (code "37") (name "Net-(J1-7)") (class "Default")
      (node (ref "J1") (pin "P$1") (pinfunction "8_P$1") (pintype "bidirectional"))
      (node (ref "J1") (pin "P$2") (pinfunction "7_P$2") (pintype "bidirectional"))
      (node (ref "R8") (pin "2") (pinfunction "2_2") (pintype "passive"))
    )
    (net (code "38") (name "Net-(J13-1)") (class "Default")
      (node (ref "J13") (pin "P$1") (pinfunction "1_P$1") (pintype "passive"))
      (node (ref "R32") (pin "1") (pinfunction "1_1") (pintype "passive"))
    )
    (net (code "39") (name "Net-(J14-1)") (class "Default")
      (node (ref "J14") (pin "P$1") (pinfunction "1_P$1") (pintype "passive"))
      (node (ref "R33") (pin "1") (pinfunction "1_1") (pintype "passive"))
    )
    (net (code "40") (name "Net-(LED1-PadC)") (class "Default")
      (node (ref "LED1") (pin "C") (pinfunction "C_C") (pintype "passive"))
      (node (ref "R10") (pin "1") (pinfunction "1_1") (pintype "passive"))
    )
    (net (code "41") (name "Net-(LED2-PadC)") (class "Default")
      (node (ref "LED2") (pin "C") (pinfunction "C_C") (pintype "passive"))
      (node (ref "R11") (pin "1") (pinfunction "1_1") (pintype "passive"))
    )
    (net (code "42") (name "Net-(LED3-PadC)") (class "Default")
      (node (ref "LED3") (pin "C") (pinfunction "C_C") (pintype "passive"))
      (node (ref "R19") (pin "1") (pinfunction "1_1") (pintype "passive"))
    )
    (net (code "43") (name "Net-(R5-Pad2)") (class "Default")
      (node (ref "R5") (pin "2") (pinfunction "2_2") (pintype "passive"))
      (node (ref "U2") (pin "P$15") (pinfunction "P$15_P$15") (pintype "bidirectional"))
    )
    (net (code "44") (name "Net-(R6-Pad2)") (class "Default")
      (node (ref "R6") (pin "2") (pinfunction "2_2") (pintype "passive"))
      (node (ref "U2") (pin "P$10") (pinfunction "P$10_P$10") (pintype "bidirectional"))
    )
    (net (code "45") (name "Net-(U1B-OSC0)") (class "Default")
      (node (ref "C16") (pin "1") (pinfunction "1_1") (pintype "passive"))
      (node (ref "U1") (pin "P$88") (pinfunction "OSC0_P$88") (pintype "bidirectional"))
      (node (ref "Y1") (pin "P$3") (pinfunction "OSC1_P$3") (pintype "bidirectional"))
    )
    (net (code "46") (name "Net-(U1B-OSC1)") (class "Default")
      (node (ref "R15") (pin "2") (pinfunction "2_2") (pintype "passive"))
      (node (ref "U1") (pin "P$89") (pinfunction "OSC1_P$89") (pintype "bidirectional"))
    )
    (net (code "47") (name "Net-(U1B-RBIAS)") (class "Default")
      (node (ref "R14") (pin "2") (pinfunction "2_2") (pintype "passive"))
      (node (ref "U1") (pin "P$59") (pinfunction "RBIAS_P$59") (pintype "bidirectional"))
    )
    (net (code "48") (name "Net-(U1B-VBAT)") (class "Default")
      (node (ref "C7") (pin "1") (pinfunction "1_1") (pintype "passive"))
      (node (ref "R13") (pin "1") (pinfunction "1_1") (pintype "passive"))
      (node (ref "U1") (pin "P$68") (pinfunction "VBAT_P$68") (pintype "bidirectional"))
    )
    (net (code "49") (name "Net-(U1B-XOSC0)") (class "Default")
      (node (ref "C19") (pin "1") (pinfunction "1_1") (pintype "passive"))
      (node (ref "U1") (pin "P$66") (pinfunction "XOSC0_P$66") (pintype "bidirectional"))
      (node (ref "Y2") (pin "P$1") (pinfunction "P$1_P$1") (pintype "bidirectional"))
    )
    (net (code "50") (name "Net-(U1B-XOSC1)") (class "Default")
      (node (ref "C18") (pin "1") (pinfunction "1_1") (pintype "passive"))
      (node (ref "U1") (pin "P$67") (pinfunction "XOSC1_P$67") (pintype "bidirectional"))
      (node (ref "Y2") (pin "P$2") (pinfunction "P$2_P$2") (pintype "bidirectional"))
    )
    (net (code "51") (name "Net-(U1B-~{RESET})") (class "Default")
      (node (ref "C17") (pin "1") (pinfunction "1_1") (pintype "passive"))
      (node (ref "R16") (pin "1") (pinfunction "1_1") (pintype "passive"))
      (node (ref "R17") (pin "2") (pinfunction "2_2") (pintype "passive"))
      (node (ref "U1") (pin "P$70") (pinfunction "~{RESET}_P$70") (pintype "bidirectional"))
    )
    (net (code "52") (name "Net-(U1B-~{WAKE})") (class "Default")
      (node (ref "R12") (pin "1") (pinfunction "1_1") (pintype "passive"))
      (node (ref "U1") (pin "P$64") (pinfunction "~{WAKE}_P$64") (pintype "bidirectional"))
    )
    (net (code "53") (name "Net-(U5-EN)") (class "Default")
      (node (ref "R18") (pin "2") (pinfunction "2_2") (pintype "passive"))
      (node (ref "U5") (pin "5") (pinfunction "EN_5") (pintype "passive"))
    )
    (net (code "54") (name "Net-(U5-NR{slash}FB)") (class "Default")
      (node (ref "C21") (pin "1") (pinfunction "1_1") (pintype "passive"))
      (node (ref "U5") (pin "4") (pinfunction "NR/FB_4") (pintype "bidirectional"))
    )
    (net (code "55") (name "Net-(U6-FB)") (class "Default")
      (node (ref "R20") (pin "1") (pinfunction "1_1") (pintype "passive"))
      (node (ref "R21") (pin "2") (pinfunction "2_2") (pintype "passive"))
      (node (ref "U6") (pin "15") (pinfunction "FB_15") (pintype "input"))
    )
    (net (code "56") (name "Net-(U8-FB)") (class "Default")
      (node (ref "R22") (pin "1") (pinfunction "1_1") (pintype "passive"))
      (node (ref "R23") (pin "2") (pinfunction "2_2") (pintype "passive"))
      (node (ref "U8") (pin "15") (pinfunction "FB_15") (pintype "input"))
    )
    (net (code "57") (name "Net-(Y1-OSC0)") (class "Default")
      (node (ref "C15") (pin "1") (pinfunction "1_1") (pintype "passive"))
      (node (ref "R15") (pin "1") (pinfunction "1_1") (pintype "passive"))
      (node (ref "Y1") (pin "P$1") (pinfunction "OSC0_P$1") (pintype "bidirectional"))
    )
    (net (code "58") (name "RX") (class "Default")
      (node (ref "J2") (pin "P7") (pinfunction "P$7_P7") (pintype "bidirectional"))
      (node (ref "U1") (pin "P$33") (pinfunction "PA0_P$33") (pintype "bidirectional"))
    )
    (net (code "59") (name "TARGET_TCK{slash}SWCLK") (class "Default")
      (node (ref "J2") (pin "P4") (pinfunction "TCK_P4") (pintype "bidirectional"))
      (node (ref "U1") (pin "P$100") (pinfunction "PC0_P$100") (pintype "bidirectional"))
    )
    (net (code "60") (name "TARGET_TDI") (class "Default")
      (node (ref "J2") (pin "P8") (pinfunction "TDI_P8") (pintype "bidirectional"))
      (node (ref "U1") (pin "P$98") (pinfunction "PC2_P$98") (pintype "bidirectional"))
    )
    (net (code "61") (name "TARGET_TDO{slash}SWO") (class "Default")
      (node (ref "J2") (pin "P6") (pinfunction "TDO_P6") (pintype "bidirectional"))
      (node (ref "U1") (pin "P$97") (pinfunction "PC3_P$97") (pintype "bidirectional"))
    )
    (net (code "62") (name "TARGET_TMS{slash}SWDIO") (class "Default")
      (node (ref "J2") (pin "P2") (pinfunction "TMS_P2") (pintype "bidirectional"))
      (node (ref "U1") (pin "P$99") (pinfunction "PC1_P$99") (pintype "bidirectional"))
    )
    (net (code "63") (name "TX") (class "Default")
      (node (ref "J2") (pin "P9") (pinfunction "GND1_P9") (pintype "bidirectional"))
      (node (ref "U1") (pin "P$34") (pinfunction "PA1_P$34") (pintype "bidirectional"))
    )
    (net (code "64") (name "unconnected-(U1A-PA2-PadP$35)") (class "Default")
      (node (ref "U1") (pin "P$35") (pinfunction "PA2_P$35") (pintype "bidirectional"))
    )
    (net (code "65") (name "unconnected-(U1A-PA3-PadP$36)") (class "Default")
      (node (ref "U1") (pin "P$36") (pinfunction "PA3_P$36") (pintype "bidirectional"))
    )
    (net (code "66") (name "unconnected-(U1A-PA4-PadP$37)") (class "Default")
      (node (ref "U1") (pin "P$37") (pinfunction "PA4_P$37") (pintype "bidirectional"))
    )
    (net (code "67") (name "unconnected-(U1A-PA5-PadP$38)") (class "Default")
      (node (ref "U1") (pin "P$38") (pinfunction "PA5_P$38") (pintype "bidirectional"))
    )
    (net (code "68") (name "unconnected-(U1A-PA6-PadP$40)") (class "Default")
      (node (ref "U1") (pin "P$40") (pinfunction "PA6_P$40") (pintype "bidirectional"))
    )
    (net (code "69") (name "unconnected-(U1A-PA7-PadP$41)") (class "Default")
      (node (ref "U1") (pin "P$41") (pinfunction "PA7_P$41") (pintype "bidirectional"))
    )
    (net (code "70") (name "unconnected-(U1A-PB0-PadP$95)") (class "Default")
      (node (ref "U1") (pin "P$95") (pinfunction "PB0_P$95") (pintype "bidirectional"))
    )
    (net (code "71") (name "unconnected-(U1A-PB1-PadP$96)") (class "Default")
      (node (ref "U1") (pin "P$96") (pinfunction "PB1_P$96") (pintype "bidirectional"))
    )
    (net (code "72") (name "unconnected-(U1A-PB2-PadP$91)") (class "Default")
      (node (ref "U1") (pin "P$91") (pinfunction "PB2_P$91") (pintype "bidirectional"))
    )
    (net (code "73") (name "unconnected-(U1A-PB3-PadP$92)") (class "Default")
      (node (ref "U1") (pin "P$92") (pinfunction "PB3_P$92") (pintype "bidirectional"))
    )
    (net (code "74") (name "unconnected-(U1A-PB4-PadP$121)") (class "Default")
      (node (ref "U1") (pin "P$121") (pinfunction "PB4_P$121") (pintype "bidirectional"))
    )
    (net (code "75") (name "unconnected-(U1A-PB5-PadP$120)") (class "Default")
      (node (ref "U1") (pin "P$120") (pinfunction "PB5_P$120") (pintype "bidirectional"))
    )
    (net (code "76") (name "unconnected-(U1A-PC4-PadP$25)") (class "Default")
      (node (ref "U1") (pin "P$25") (pinfunction "PC4_P$25") (pintype "bidirectional"))
    )
    (net (code "77") (name "unconnected-(U1A-PC5-PadP$24)") (class "Default")
      (node (ref "U1") (pin "P$24") (pinfunction "PC5_P$24") (pintype "bidirectional"))
    )
    (net (code "78") (name "unconnected-(U1A-PC6-PadP$23)") (class "Default")
      (node (ref "U1") (pin "P$23") (pinfunction "PC6_P$23") (pintype "bidirectional"))
    )
    (net (code "79") (name "unconnected-(U1A-PC7-PadP$22)") (class "Default")
      (node (ref "U1") (pin "P$22") (pinfunction "PC7_P$22") (pintype "bidirectional"))
    )
    (net (code "80") (name "unconnected-(U1A-PE0-PadP$15)") (class "Default")
      (node (ref "U1") (pin "P$15") (pinfunction "PE0_P$15") (pintype "bidirectional"))
    )
    (net (code "81") (name "unconnected-(U1A-PE1-PadP$14)") (class "Default")
      (node (ref "U1") (pin "P$14") (pinfunction "PE1_P$14") (pintype "bidirectional"))
    )
    (net (code "82") (name "unconnected-(U1A-PE2-PadP$13)") (class "Default")
      (node (ref "U1") (pin "P$13") (pinfunction "PE2_P$13") (pintype "bidirectional"))
    )
    (net (code "83") (name "unconnected-(U1A-PE3-PadP$12)") (class "Default")
      (node (ref "U1") (pin "P$12") (pinfunction "PE3_P$12") (pintype "bidirectional"))
    )
    (net (code "84") (name "unconnected-(U1A-PE4-PadP$123)") (class "Default")
      (node (ref "U1") (pin "P$123") (pinfunction "PE4_P$123") (pintype "bidirectional"))
    )
    (net (code "85") (name "unconnected-(U1A-PE5-PadP$124)") (class "Default")
      (node (ref "U1") (pin "P$124") (pinfunction "PE5_P$124") (pintype "bidirectional"))
    )
    (net (code "86") (name "unconnected-(U1A-PF1-PadP$43)") (class "Default")
      (node (ref "U1") (pin "P$43") (pinfunction "PF1_P$43") (pintype "bidirectional"))
    )
    (net (code "87") (name "unconnected-(U1A-PF2-PadP$44)") (class "Default")
      (node (ref "U1") (pin "P$44") (pinfunction "PF2_P$44") (pintype "bidirectional"))
    )
    (net (code "88") (name "unconnected-(U1A-PF3-PadP$45)") (class "Default")
      (node (ref "U1") (pin "P$45") (pinfunction "PF3_P$45") (pintype "bidirectional"))
    )
    (net (code "89") (name "unconnected-(U1A-PG0-PadP$49)") (class "Default")
      (node (ref "U1") (pin "P$49") (pinfunction "PG0_P$49") (pintype "bidirectional"))
    )
    (net (code "90") (name "unconnected-(U1A-PG1-PadP$50)") (class "Default")
      (node (ref "U1") (pin "P$50") (pinfunction "PG1_P$50") (pintype "bidirectional"))
    )
    (net (code "91") (name "unconnected-(U1A-PH0-PadP$29)") (class "Default")
      (node (ref "U1") (pin "P$29") (pinfunction "PH0_P$29") (pintype "bidirectional"))
    )
    (net (code "92") (name "unconnected-(U1A-PH1-PadP$30)") (class "Default")
      (node (ref "U1") (pin "P$30") (pinfunction "PH1_P$30") (pintype "bidirectional"))
    )
    (net (code "93") (name "unconnected-(U1A-PH2-PadP$31)") (class "Default")
      (node (ref "U1") (pin "P$31") (pinfunction "PH2_P$31") (pintype "bidirectional"))
    )
    (net (code "94") (name "unconnected-(U1A-PH3-PadP$32)") (class "Default")
      (node (ref "U1") (pin "P$32") (pinfunction "PH3_P$32") (pintype "bidirectional"))
    )
    (net (code "95") (name "unconnected-(U1A-PJ0-PadP$116)") (class "Default")
      (node (ref "U1") (pin "P$116") (pinfunction "PJ0_P$116") (pintype "bidirectional"))
    )
    (net (code "96") (name "unconnected-(U1A-PJ1-PadP$117)") (class "Default")
      (node (ref "U1") (pin "P$117") (pinfunction "PJ1_P$117") (pintype "bidirectional"))
    )
    (net (code "97") (name "unconnected-(U1A-PK0-PadP$18)") (class "Default")
      (node (ref "U1") (pin "P$18") (pinfunction "PK0_P$18") (pintype "bidirectional"))
    )
    (net (code "98") (name "unconnected-(U1A-PK1-PadP$19)") (class "Default")
      (node (ref "U1") (pin "P$19") (pinfunction "PK1_P$19") (pintype "bidirectional"))
    )
    (net (code "99") (name "unconnected-(U1A-PK2-PadP$20)") (class "Default")
      (node (ref "U1") (pin "P$20") (pinfunction "PK2_P$20") (pintype "bidirectional"))
    )
    (net (code "100") (name "unconnected-(U1A-PK3-PadP$21)") (class "Default")
      (node (ref "U1") (pin "P$21") (pinfunction "PK3_P$21") (pintype "bidirectional"))
    )
    (net (code "101") (name "unconnected-(U1A-PK4-PadP$63)") (class "Default")
      (node (ref "U1") (pin "P$63") (pinfunction "PK4_P$63") (pintype "bidirectional"))
    )
    (net (code "102") (name "unconnected-(U1A-PK5-PadP$62)") (class "Default")
      (node (ref "U1") (pin "P$62") (pinfunction "PK5_P$62") (pintype "bidirectional"))
    )
    (net (code "103") (name "unconnected-(U1A-PK6-PadP$61)") (class "Default")
      (node (ref "U1") (pin "P$61") (pinfunction "PK6_P$61") (pintype "bidirectional"))
    )
    (net (code "104") (name "unconnected-(U1A-PK7-PadP$60)") (class "Default")
      (node (ref "U1") (pin "P$60") (pinfunction "PK7_P$60") (pintype "bidirectional"))
    )
    (net (code "105") (name "unconnected-(U1A-PL0-PadP$81)") (class "Default")
      (node (ref "U1") (pin "P$81") (pinfunction "PL0_P$81") (pintype "bidirectional"))
    )
    (net (code "106") (name "unconnected-(U1A-PL1-PadP$82)") (class "Default")
      (node (ref "U1") (pin "P$82") (pinfunction "PL1_P$82") (pintype "bidirectional"))
    )
    (net (code "107") (name "unconnected-(U1A-PL2-PadP$83)") (class "Default")
      (node (ref "U1") (pin "P$83") (pinfunction "PL2_P$83") (pintype "bidirectional"))
    )
    (net (code "108") (name "unconnected-(U1A-PL3-PadP$84)") (class "Default")
      (node (ref "U1") (pin "P$84") (pinfunction "PL3_P$84") (pintype "bidirectional"))
    )
    (net (code "109") (name "unconnected-(U1A-PL4-PadP$85)") (class "Default")
      (node (ref "U1") (pin "P$85") (pinfunction "PL4_P$85") (pintype "bidirectional"))
    )
    (net (code "110") (name "unconnected-(U1A-PL5-PadP$86)") (class "Default")
      (node (ref "U1") (pin "P$86") (pinfunction "PL5_P$86") (pintype "bidirectional"))
    )
    (net (code "111") (name "unconnected-(U1A-PL6-PadP$94)") (class "Default")
      (node (ref "U1") (pin "P$94") (pinfunction "PL6_P$94") (pintype "bidirectional"))
    )
    (net (code "112") (name "unconnected-(U1A-PL7-PadP$93)") (class "Default")
      (node (ref "U1") (pin "P$93") (pinfunction "PL7_P$93") (pintype "bidirectional"))
    )
    (net (code "113") (name "unconnected-(U1A-PM0-PadP$78)") (class "Default")
      (node (ref "U1") (pin "P$78") (pinfunction "PM0_P$78") (pintype "bidirectional"))
    )
    (net (code "114") (name "unconnected-(U1A-PM1-PadP$77)") (class "Default")
      (node (ref "U1") (pin "P$77") (pinfunction "PM1_P$77") (pintype "bidirectional"))
    )
    (net (code "115") (name "unconnected-(U1A-PM2-PadP$76)") (class "Default")
      (node (ref "U1") (pin "P$76") (pinfunction "PM2_P$76") (pintype "bidirectional"))
    )
    (net (code "116") (name "unconnected-(U1A-PM3-PadP$75)") (class "Default")
      (node (ref "U1") (pin "P$75") (pinfunction "PM3_P$75") (pintype "bidirectional"))
    )
    (net (code "117") (name "unconnected-(U1A-PM4-PadP$74)") (class "Default")
      (node (ref "U1") (pin "P$74") (pinfunction "PM4_P$74") (pintype "bidirectional"))
    )
    (net (code "118") (name "unconnected-(U1A-PM5-PadP$73)") (class "Default")
      (node (ref "U1") (pin "P$73") (pinfunction "PM5_P$73") (pintype "bidirectional"))
    )
    (net (code "119") (name "unconnected-(U1A-PM6-PadP$72)") (class "Default")
      (node (ref "U1") (pin "P$72") (pinfunction "PM6_P$72") (pintype "bidirectional"))
    )
    (net (code "120") (name "unconnected-(U1A-PM7-PadP$71)") (class "Default")
      (node (ref "U1") (pin "P$71") (pinfunction "PM7_P$71") (pintype "bidirectional"))
    )
    (net (code "121") (name "unconnected-(U1A-PN0-PadP$107)") (class "Default")
      (node (ref "U1") (pin "P$107") (pinfunction "PN0_P$107") (pintype "bidirectional"))
    )
    (net (code "122") (name "unconnected-(U1A-PN1-PadP$108)") (class "Default")
      (node (ref "U1") (pin "P$108") (pinfunction "PN1_P$108") (pintype "bidirectional"))
    )
    (net (code "123") (name "unconnected-(U1A-PN2-PadP$109)") (class "Default")
      (node (ref "U1") (pin "P$109") (pinfunction "PN2_P$109") (pintype "bidirectional"))
    )
    (net (code "124") (name "unconnected-(U1A-PN3-PadP$110)") (class "Default")
      (node (ref "U1") (pin "P$110") (pinfunction "PN3_P$110") (pintype "bidirectional"))
    )
    (net (code "125") (name "unconnected-(U1A-PN4-PadP$111)") (class "Default")
      (node (ref "U1") (pin "P$111") (pinfunction "PN4_P$111") (pintype "bidirectional"))
    )
    (net (code "126") (name "unconnected-(U1A-PN5-PadP$112)") (class "Default")
      (node (ref "U1") (pin "P$112") (pinfunction "PN5_P$112") (pintype "bidirectional"))
    )
    (net (code "127") (name "unconnected-(U1A-PP0-PadP$118)") (class "Default")
      (node (ref "U1") (pin "P$118") (pinfunction "PP0_P$118") (pintype "bidirectional"))
    )
    (net (code "128") (name "unconnected-(U1A-PP1-PadP$119)") (class "Default")
      (node (ref "U1") (pin "P$119") (pinfunction "PP1_P$119") (pintype "bidirectional"))
    )
    (net (code "129") (name "unconnected-(U1A-PP2-PadP$103)") (class "Default")
      (node (ref "U1") (pin "P$103") (pinfunction "PP2_P$103") (pintype "bidirectional"))
    )
    (net (code "130") (name "unconnected-(U1A-PP3-PadP$104)") (class "Default")
      (node (ref "U1") (pin "P$104") (pinfunction "PP3_P$104") (pintype "bidirectional"))
    )
    (net (code "131") (name "unconnected-(U1A-PP4-PadP$105)") (class "Default")
      (node (ref "U1") (pin "P$105") (pinfunction "PP4_P$105") (pintype "bidirectional"))
    )
    (net (code "132") (name "unconnected-(U1A-PP5-PadP$106)") (class "Default")
      (node (ref "U1") (pin "P$106") (pinfunction "PP5_P$106") (pintype "bidirectional"))
    )
    (net (code "133") (name "unconnected-(U1A-PQ0-PadP$5)") (class "Default")
      (node (ref "U1") (pin "P$5") (pinfunction "PQ0_P$5") (pintype "bidirectional"))
    )
    (net (code "134") (name "unconnected-(U1A-PQ1-PadP$6)") (class "Default")
      (node (ref "U1") (pin "P$6") (pinfunction "PQ1_P$6") (pintype "bidirectional"))
    )
    (net (code "135") (name "unconnected-(U1A-PQ2-PadP$11)") (class "Default")
      (node (ref "U1") (pin "P$11") (pinfunction "PQ2_P$11") (pintype "bidirectional"))
    )
    (net (code "136") (name "unconnected-(U1A-PQ3-PadP$27)") (class "Default")
      (node (ref "U1") (pin "P$27") (pinfunction "PQ3_P$27") (pintype "bidirectional"))
    )
    (net (code "137") (name "unconnected-(U1A-PQ4-PadP$102)") (class "Default")
      (node (ref "U1") (pin "P$102") (pinfunction "PQ4_P$102") (pintype "bidirectional"))
    )
    (net (code "138") (name "unconnected-(U1B-~{HIB}-PadP$65)") (class "Default")
      (node (ref "U1") (pin "P$65") (pinfunction "~{HIB}_P$65") (pintype "bidirectional"))
    )
    (net (code "139") (name "unconnected-(Y1-NC2-PadP$2)") (class "Default")
      (node (ref "Y1") (pin "P$2") (pinfunction "NC2_P$2") (pintype "bidirectional"))
    )
    (net (code "140") (name "unconnected-(Y1-NC4-PadP$4)") (class "Default")
      (node (ref "Y1") (pin "P$4") (pinfunction "NC4_P$4") (pintype "bidirectional"))
    )
    (net (code "141") (name "~{RESET}") (class "Default")
      (node (ref "J2") (pin "P10") (pinfunction "~{RESET}_P10") (pintype "bidirectional"))
      (node (ref "R16") (pin "2") (pinfunction "2_2") (pintype "passive"))
      (node (ref "S1") (pin "P$3") (pinfunction "1_P$3") (pintype "passive"))
      (node (ref "S1") (pin "P$4") (pinfunction "1_P$4") (pintype "passive"))
    )
  )
)
